# AUDIO.net
KiCad netlist of a schematic drawn in Altium Designer
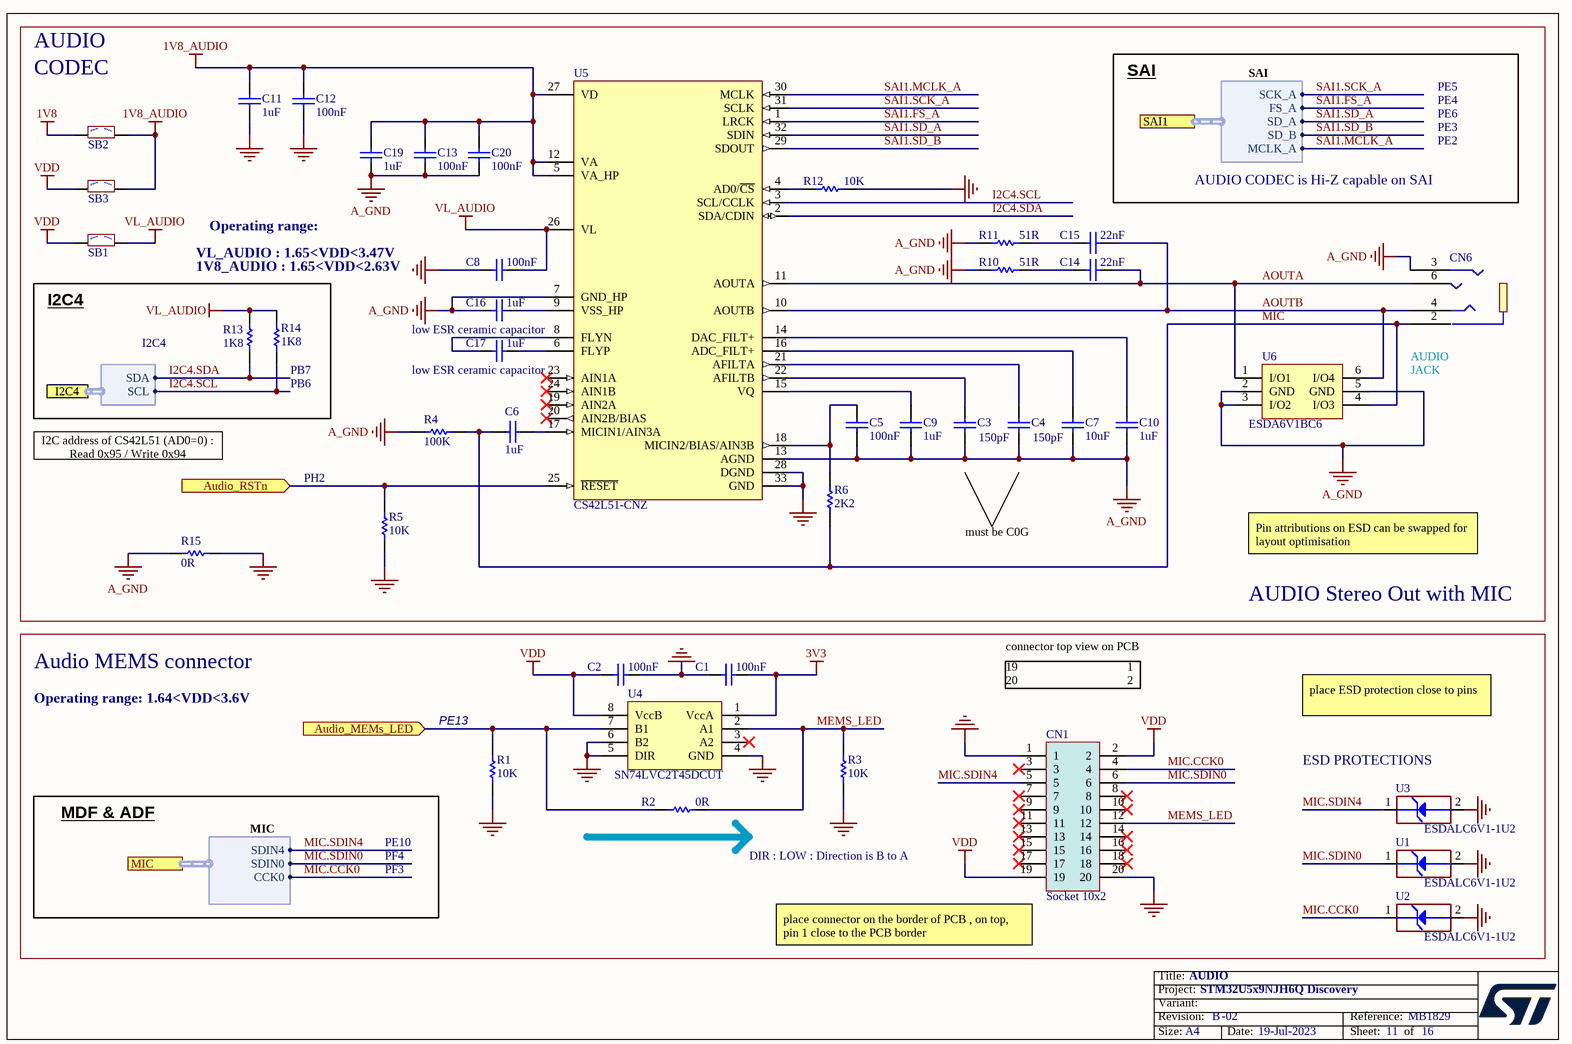
[diagram p0: AUDIO.SchDoc]

(export (version "E")
  (design (tool "Eeschema 10.0.6"))
  (components
    (comp (ref "C1")
      (value "100nF")
      (footprint "MCD_PARTS:C0402")
      (description "Capacitor, MLCC, 100nF, 16V, X7R, +/-10%, 0402, T=0.5mm")
      (fields
        (field (name "INTERNAL_PART_NUMBER") "MCD-00006")
        (field (name "MANUFACTURER_PART_NUMBER") "CC0402KRX7R7BB104")
      )
      (libsource (lib "MCD_PARTS_database") (part "Capacitor"))
    )
    (comp (ref "C2")
      (value "100nF")
      (footprint "MCD_PARTS:C0402")
      (description "Capacitor, MLCC, 100nF, 16V, X7R, +/-10%, 0402, T=0.5mm")
      (fields
        (field (name "INTERNAL_PART_NUMBER") "MCD-00006")
        (field (name "MANUFACTURER_PART_NUMBER") "CC0402KRX7R7BB104")
      )
      (libsource (lib "MCD_PARTS_database") (part "Capacitor"))
    )
    (comp (ref "C3")
      (value "150pF")
      (footprint "MCD_PARTS:C0603")
      (description "Capacitor, MLCC, 150pF, 50V, COG, +/-5%, 0603, T=0.8mm")
      (fields
        (field (name "INTERNAL_PART_NUMBER") "MCD-00304")
        (field (name "MANUFACTURER_PART_NUMBER") "CC0603JRNPO9BN151")
      )
      (libsource (lib "MCD_PARTS_database") (part "Capacitor"))
    )
    (comp (ref "C4")
      (value "150pF")
      (footprint "MCD_PARTS:C0603")
      (description "Capacitor, MLCC, 150pF, 50V, COG, +/-5%, 0603, T=0.8mm")
      (fields
        (field (name "INTERNAL_PART_NUMBER") "MCD-00304")
        (field (name "MANUFACTURER_PART_NUMBER") "CC0603JRNPO9BN151")
      )
      (libsource (lib "MCD_PARTS_database") (part "Capacitor"))
    )
    (comp (ref "C5")
      (value "100nF")
      (footprint "MCD_PARTS:C0402")
      (description "Capacitor, MLCC, 100nF, 16V, X7R, +/-10%, 0402, T=0.5mm")
      (fields
        (field (name "INTERNAL_PART_NUMBER") "MCD-00006")
        (field (name "MANUFACTURER_PART_NUMBER") "CC0402KRX7R7BB104")
      )
      (libsource (lib "MCD_PARTS_database") (part "Capacitor"))
    )
    (comp (ref "C6")
      (value "1uF")
      (footprint "MCD_PARTS:C0402")
      (description "Capacitor, MLCC, 1uF, 10V, X5R, +/-10%, 0402, T=0.5mm")
      (fields
        (field (name "INTERNAL_PART_NUMBER") "MCD-01722")
        (field (name "MANUFACTURER_PART_NUMBER") "CC0402KRX5R6BB105")
      )
      (libsource (lib "MCD_PARTS_database") (part "Capacitor"))
    )
    (comp (ref "C7")
      (value "10uF")
      (footprint "MCD_PARTS:C0603")
      (description "Capacitor, MLCC, 10uF, 6V3, X5R, +/-10%, 0603, T=0.8mm")
      (fields
        (field (name "INTERNAL_PART_NUMBER") "MCD-00243")
        (field (name "MANUFACTURER_PART_NUMBER") "CC0603KRX5R5BB106")
      )
      (libsource (lib "MCD_PARTS_database") (part "Capacitor"))
    )
    (comp (ref "C8")
      (value "100nF")
      (footprint "MCD_PARTS:C0402")
      (description "Capacitor, MLCC, 100nF, 16V, X7R, +/-10%, 0402, T=0.5mm")
      (fields
        (field (name "INTERNAL_PART_NUMBER") "MCD-00006")
        (field (name "MANUFACTURER_PART_NUMBER") "CC0402KRX7R7BB104")
      )
      (libsource (lib "MCD_PARTS_database") (part "Capacitor"))
    )
    (comp (ref "C9")
      (value "1uF")
      (footprint "MCD_PARTS:C0402")
      (description "Capacitor, MLCC, 1uF, 10V, X5R, +/-10%, 0402, T=0.5mm")
      (fields
        (field (name "INTERNAL_PART_NUMBER") "MCD-01722")
        (field (name "MANUFACTURER_PART_NUMBER") "CC0402KRX5R6BB105")
      )
      (libsource (lib "MCD_PARTS_database") (part "Capacitor"))
    )
    (comp (ref "C10")
      (value "1uF")
      (footprint "MCD_PARTS:C0402")
      (description "Capacitor, MLCC, 1uF, 10V, X5R, +/-10%, 0402, T=0.5mm")
      (fields
        (field (name "INTERNAL_PART_NUMBER") "MCD-01722")
        (field (name "MANUFACTURER_PART_NUMBER") "CC0402KRX5R6BB105")
      )
      (libsource (lib "MCD_PARTS_database") (part "Capacitor"))
    )
    (comp (ref "C11")
      (value "1uF")
      (footprint "MCD_PARTS:C0402")
      (description "Capacitor, MLCC, 1uF, 10V, X5R, +/-10%, 0402, T=0.5mm")
      (fields
        (field (name "INTERNAL_PART_NUMBER") "MCD-01722")
        (field (name "MANUFACTURER_PART_NUMBER") "CC0402KRX5R6BB105")
      )
      (libsource (lib "MCD_PARTS_database") (part "Capacitor"))
    )
    (comp (ref "C12")
      (value "100nF")
      (footprint "MCD_PARTS:C0402")
      (description "Capacitor, MLCC, 100nF, 16V, X7R, +/-10%, 0402, T=0.5mm")
      (fields
        (field (name "INTERNAL_PART_NUMBER") "MCD-00006")
        (field (name "MANUFACTURER_PART_NUMBER") "CC0402KRX7R7BB104")
      )
      (libsource (lib "MCD_PARTS_database") (part "Capacitor"))
    )
    (comp (ref "C13")
      (value "100nF")
      (footprint "MCD_PARTS:C0402")
      (description "Capacitor, MLCC, 100nF, 16V, X7R, +/-10%, 0402, T=0.5mm")
      (fields
        (field (name "INTERNAL_PART_NUMBER") "MCD-00006")
        (field (name "MANUFACTURER_PART_NUMBER") "CC0402KRX7R7BB104")
      )
      (libsource (lib "MCD_PARTS_database") (part "Capacitor"))
    )
    (comp (ref "C14")
      (value "22nF")
      (footprint "MCD_PARTS:C0402")
      (description "Capacitor, MLCC, 22nF, 16V, X7R, +/-10%, 0402, T=0.5mm")
      (fields
        (field (name "INTERNAL_PART_NUMBER") "MCD-00202")
        (field (name "MANUFACTURER_PART_NUMBER") "CC0402KRX7R7BB223")
      )
      (libsource (lib "MCD_PARTS_database") (part "Capacitor"))
    )
    (comp (ref "C15")
      (value "22nF")
      (footprint "MCD_PARTS:C0402")
      (description "Capacitor, MLCC, 22nF, 16V, X7R, +/-10%, 0402, T=0.5mm")
      (fields
        (field (name "INTERNAL_PART_NUMBER") "MCD-00202")
        (field (name "MANUFACTURER_PART_NUMBER") "CC0402KRX7R7BB223")
      )
      (libsource (lib "MCD_PARTS_database") (part "Capacitor"))
    )
    (comp (ref "C16")
      (value "1uF")
      (footprint "MCD_PARTS:C0603")
      (description "Capacitor, MLCC, 1uF, 16V, X5R, +/-10%, 0603, T=0.8mm")
      (fields
        (field (name "INTERNAL_PART_NUMBER") "MCD-00010")
        (field (name "MANUFACTURER_PART_NUMBER") "CC0603KRX5R7BB105")
      )
      (libsource (lib "MCD_PARTS_database") (part "Capacitor"))
    )
    (comp (ref "C17")
      (value "1uF")
      (footprint "MCD_PARTS:C0603")
      (description "Capacitor, MLCC, 1uF, 16V, X5R, +/-10%, 0603, T=0.8mm")
      (fields
        (field (name "INTERNAL_PART_NUMBER") "MCD-00010")
        (field (name "MANUFACTURER_PART_NUMBER") "CC0603KRX5R7BB105")
      )
      (libsource (lib "MCD_PARTS_database") (part "Capacitor"))
    )
    (comp (ref "C19")
      (value "1uF")
      (footprint "MCD_PARTS:C0402")
      (description "Capacitor, MLCC, 1uF, 10V, X5R, +/-10%, 0402, T=0.5mm")
      (fields
        (field (name "INTERNAL_PART_NUMBER") "MCD-01722")
        (field (name "MANUFACTURER_PART_NUMBER") "CC0402KRX5R6BB105")
      )
      (libsource (lib "MCD_PARTS_database") (part "Capacitor"))
    )
    (comp (ref "C20")
      (value "100nF")
      (footprint "MCD_PARTS:C0402")
      (description "Capacitor, MLCC, 100nF, 16V, X7R, +/-10%, 0402, T=0.5mm")
      (fields
        (field (name "INTERNAL_PART_NUMBER") "MCD-00006")
        (field (name "MANUFACTURER_PART_NUMBER") "CC0402KRX7R7BB104")
      )
      (libsource (lib "MCD_PARTS_database") (part "Capacitor"))
    )
    (comp (ref "CN1")
      (value "Socket 10x2")
      (footprint "MCD_PARTS:CON_FCI_20021311-XXX20XXLF")
      (description "Socket, 10x2, 1.27mm, VR, TH, T=4.30mm/2.40mm")
      (fields (field (name "INTERNAL_PART_NUMBER") "MCD-00147") (field (name "MANUFACTURER") "AMPHENOL ICC"))
      (libsource (lib "MCD_PARTS_database") (part "Socket 10x2"))
    )
    (comp (ref "CN6")
      (value "Jack_PJ3028B-3_4P")
      (footprint "MCD_PARTS:CON_PHONE-JACK-3P5_HY_PJ3028B")
      (description "Jack_ Socket-Stereo, 3.5mm, 4 pins, RA, SMD, T=5mm")
      (fields
        (field (name "INTERNAL_PART_NUMBER") "MCD-00263")
        (field (name "MANUFACTURER_PART_NUMBER") "PJ3028B-3_4P")
      )
      (libsource (lib "MCD_PARTS_database") (part "Jack_PJ3028B-3_4P"))
    )
    (comp (ref "R1")
      (value "10K")
      (footprint "MCD_PARTS:R0402")
      (description "Resistor, 10K, 0402, +/-1%, 1/16W")
      (fields
        (field (name "INTERNAL_PART_NUMBER") "MCD-00053")
        (field (name "MANUFACTURER_PART_NUMBER") "RC0402FR-0710KL")
      )
      (libsource (lib "MCD_PARTS_database") (part "Resistor"))
    )
    (comp (ref "R2")
      (value "0R")
      (footprint "MCD_PARTS:R0402")
      (description "Resistor, 0R, 0402, +/-5%, 1/16W")
      (fields
        (field (name "INTERNAL_PART_NUMBER") "MCD-00052")
        (field (name "MANUFACTURER_PART_NUMBER") "RC0402JR-070RL")
      )
      (libsource (lib "MCD_PARTS_database") (part "Resistor"))
    )
    (comp (ref "R3")
      (value "10K")
      (footprint "MCD_PARTS:R0402")
      (description "Resistor, 10K, 0402, +/-1%, 1/16W")
      (fields
        (field (name "INTERNAL_PART_NUMBER") "MCD-00053")
        (field (name "MANUFACTURER_PART_NUMBER") "RC0402FR-0710KL")
      )
      (libsource (lib "MCD_PARTS_database") (part "Resistor"))
    )
    (comp (ref "R4")
      (value "100K")
      (footprint "MCD_PARTS:R0402")
      (description "Resistor, 100K, 0402, +/-1%, 1/16W")
      (fields
        (field (name "INTERNAL_PART_NUMBER") "MCD-00059")
        (field (name "MANUFACTURER_PART_NUMBER") "RC0402FR-07100KL")
      )
      (libsource (lib "MCD_PARTS_database") (part "Resistor"))
    )
    (comp (ref "R5")
      (value "10K")
      (footprint "MCD_PARTS:R0402")
      (description "Resistor, 10K, 0402, +/-1%, 1/16W")
      (fields
        (field (name "INTERNAL_PART_NUMBER") "MCD-00053")
        (field (name "MANUFACTURER_PART_NUMBER") "RC0402FR-0710KL")
      )
      (libsource (lib "MCD_PARTS_database") (part "Resistor"))
    )
    (comp (ref "R6")
      (value "2K2")
      (footprint "MCD_PARTS:R0402")
      (description "Resistor, 2K2, 0402, +/-1%, 1/16W")
      (fields
        (field (name "INTERNAL_PART_NUMBER") "MCD-00057")
        (field (name "MANUFACTURER_PART_NUMBER") "RC0402FR-072K2L")
      )
      (libsource (lib "MCD_PARTS_database") (part "Resistor"))
    )
    (comp (ref "R10")
      (value "51R")
      (footprint "MCD_PARTS:R0402")
      (description "Resistor, 51R, 0402, +/-1%, 1/16W")
      (fields
        (field (name "INTERNAL_PART_NUMBER") "MCD-00485")
        (field (name "MANUFACTURER_PART_NUMBER") "RC0402FR-0751RL")
      )
      (libsource (lib "MCD_PARTS_database") (part "Resistor"))
    )
    (comp (ref "R11")
      (value "51R")
      (footprint "MCD_PARTS:R0402")
      (description "Resistor, 51R, 0402, +/-1%, 1/16W")
      (fields
        (field (name "INTERNAL_PART_NUMBER") "MCD-00485")
        (field (name "MANUFACTURER_PART_NUMBER") "RC0402FR-0751RL")
      )
      (libsource (lib "MCD_PARTS_database") (part "Resistor"))
    )
    (comp (ref "R12")
      (value "10K")
      (footprint "MCD_PARTS:R0402")
      (description "Resistor, 10K, 0402, +/-1%, 1/16W")
      (fields
        (field (name "INTERNAL_PART_NUMBER") "MCD-00053")
        (field (name "MANUFACTURER_PART_NUMBER") "RC0402FR-0710KL")
      )
      (libsource (lib "MCD_PARTS_database") (part "Resistor"))
    )
    (comp (ref "R13")
      (value "1K8")
      (footprint "MCD_PARTS:R0402")
      (description "Resistor, 1K8, 0402, +/-1%, 1/16W")
      (fields
        (field (name "INTERNAL_PART_NUMBER") "MCD-00409")
        (field (name "MANUFACTURER_PART_NUMBER") "RC0402FR-071K8L")
      )
      (libsource (lib "MCD_PARTS_database") (part "Resistor"))
    )
    (comp (ref "R14")
      (value "1K8")
      (footprint "MCD_PARTS:R0402")
      (description "Resistor, 1K8, 0402, +/-1%, 1/16W")
      (fields
        (field (name "INTERNAL_PART_NUMBER") "MCD-00409")
        (field (name "MANUFACTURER_PART_NUMBER") "RC0402FR-071K8L")
      )
      (libsource (lib "MCD_PARTS_database") (part "Resistor"))
    )
    (comp (ref "R15")
      (value "0R")
      (footprint "MCD_PARTS:R0402")
      (description "Resistor, 0R, 0402, +/-5%, 1/16W")
      (fields
        (field (name "INTERNAL_PART_NUMBER") "MCD-00052")
        (field (name "MANUFACTURER_PART_NUMBER") "RC0402JR-070RL")
      )
      (libsource (lib "MCD_PARTS_database") (part "Resistor"))
    )
    (comp (ref "SB1")
      (value "SB_OFF")
      (footprint "MCD_PARTS:SOLDER-BRIDGE_R0402-0R")
      (description "Solder Bridge 0402 OFF")
      (fields
        (field (name "INTERNAL_PART_NUMBER") "MCD-02162")
        (field (name "MANUFACTURER_PART_NUMBER") "RC0402JR-070RL")
      )
      (libsource (lib "MCD_PARTS_database") (part "SB_OFF"))
    )
    (comp (ref "SB2")
      (value "SB_OFF")
      (footprint "MCD_PARTS:SOLDER-BRIDGE_R0402-0R")
      (description "Solder Bridge 0402 OFF")
      (fields
        (field (name "INTERNAL_PART_NUMBER") "MCD-02162")
        (field (name "MANUFACTURER_PART_NUMBER") "RC0402JR-070RL")
      )
      (libsource (lib "MCD_PARTS_database") (part "SB_OFF"))
    )
    (comp (ref "SB3")
      (value "SB_OFF")
      (footprint "MCD_PARTS:SOLDER-BRIDGE_R0402-0R")
      (description "Solder Bridge 0402 OFF")
      (fields
        (field (name "INTERNAL_PART_NUMBER") "MCD-02162")
        (field (name "MANUFACTURER_PART_NUMBER") "RC0402JR-070RL")
      )
      (libsource (lib "MCD_PARTS_database") (part "SB_OFF"))
    )
    (comp (ref "U1")
      (value "ESDALC6V1-1U2")
      (footprint "MCD_PARTS:ESD_ST0201")
      (description "ESD protection 6V1")
      (fields
        (field (name "INTERNAL_PART_NUMBER") "MCD-00170")
        (field (name "MANUFACTURER") "STMICROELECTRONICS")
      )
      (libsource (lib "MCD_PARTS_database") (part "ESD-TRANSIL"))
    )
    (comp (ref "U2")
      (value "ESDALC6V1-1U2")
      (footprint "MCD_PARTS:ESD_ST0201")
      (description "ESD protection 6V1")
      (fields
        (field (name "INTERNAL_PART_NUMBER") "MCD-00170")
        (field (name "MANUFACTURER") "STMICROELECTRONICS")
      )
      (libsource (lib "MCD_PARTS_database") (part "ESD-TRANSIL"))
    )
    (comp (ref "U3")
      (value "ESDALC6V1-1U2")
      (footprint "MCD_PARTS:ESD_ST0201")
      (description "ESD protection 6V1")
      (fields
        (field (name "INTERNAL_PART_NUMBER") "MCD-00170")
        (field (name "MANUFACTURER") "STMICROELECTRONICS")
      )
      (libsource (lib "MCD_PARTS_database") (part "ESD-TRANSIL"))
    )
    (comp (ref "U4")
      (value "SN74LVC2T45DCUT")
      (footprint "MCD_PARTS:ICC_VSSOP8_DCU_R-PDSO-G8_2X2P30_P050")
      (description "Dual bit dual supply bus transceiver")
      (fields
        (field (name "INTERNAL_PART_NUMBER") "MCD-00264")
        (field (name "MANUFACTURER") "TEXAS INSTRUMENTS")
      )
      (libsource (lib "MCD_PARTS_database") (part "SN74LVC2T45DCUT"))
    )
    (comp (ref "U5")
      (value "CS42L51-CNZ")
      (footprint "MCD_PARTS:ICC_QFN32-EPAD_5X5_P050")
      (description "Low-Power, Stereo Codec with Headphone Amp")
      (fields (field (name "INTERNAL_PART_NUMBER") "MCD-00265") (field (name "MANUFACTURER") "CIRRUS LOGIC"))
      (libsource (lib "MCD_PARTS_database") (part "CS42L51-CNZ"))
    )
    (comp (ref "U6")
      (value "ESDA6V1BC6")
      (footprint "MCD_PARTS:ESD_SOT23-6L")
      (description "Quad Bidir ESD protection")
      (fields
        (field (name "INTERNAL_PART_NUMBER") "MCD-00247")
        (field (name "MANUFACTURER") "STMICROELECTRONICS")
      )
      (libsource (lib "MCD_PARTS_database") (part "ESDA6V1BC6"))
    )
  )
  (nets
    (net (code "3") (name "/AOUTA") (class "Default")
      (node (ref "C14") (pin "2") (pinfunction "2_2") (pintype "passive"))
      (node (ref "CN6") (pin "6") (pintype "passive"))
      (node (ref "U5") (pin "11") (pinfunction "AOUTA_11") (pintype "output"))
      (node (ref "U6") (pin "1") (pinfunction "I/O1_1") (pintype "passive"))
    )
    (net (code "4") (name "/AOUTB") (class "Default")
      (node (ref "C15") (pin "2") (pinfunction "2_2") (pintype "passive"))
      (node (ref "CN6") (pin "4") (pintype "passive"))
      (node (ref "U5") (pin "10") (pinfunction "AOUTB_10") (pintype "output"))
      (node (ref "U6") (pin "6") (pinfunction "I/O4_6") (pintype "passive"))
    )
    (net (code "5") (name "/Audio_MEMs_LED") (class "Default")
      (node (ref "R1") (pin "2") (pinfunction "2_2") (pintype "passive"))
      (node (ref "R2") (pin "1") (pinfunction "1_1") (pintype "passive"))
      (node (ref "U4") (pin "7") (pinfunction "B1_7") (pintype "passive"))
    )
    (net (code "6") (name "/Audio_RSTn") (class "Default")
      (node (ref "R5") (pin "2") (pinfunction "2_2") (pintype "passive"))
      (node (ref "U5") (pin "25") (pinfunction "~{RESET}_25") (pintype "input"))
    )
    (net (code "7") (name "/I2C4.SCL") (class "Default")
      (node (ref "R14") (pin "1") (pinfunction "1_1") (pintype "passive"))
      (node (ref "U5") (pin "3") (pinfunction "SCL/CCLK_3") (pintype "input"))
    )
    (net (code "8") (name "/I2C4.SDA") (class "Default")
      (node (ref "R13") (pin "1") (pinfunction "1_1") (pintype "passive"))
      (node (ref "U5") (pin "2") (pinfunction "SDA/CDIN_2") (pintype "bidirectional"))
    )
    (net (code "9") (name "/MEMS_LED") (class "Default")
      (node (ref "CN1") (pin "12") (pinfunction "12_12") (pintype "passive"))
      (node (ref "R2") (pin "2") (pinfunction "2_2") (pintype "passive"))
      (node (ref "R3") (pin "2") (pinfunction "2_2") (pintype "passive"))
      (node (ref "U4") (pin "2") (pinfunction "A1_2") (pintype "passive"))
    )
    (net (code "10") (name "/MIC") (class "Default")
      (node (ref "C6") (pin "1") (pinfunction "1_1") (pintype "passive"))
      (node (ref "CN6") (pin "2") (pintype "passive"))
      (node (ref "R4") (pin "2") (pinfunction "2_2") (pintype "passive"))
      (node (ref "R6") (pin "1") (pinfunction "1_1") (pintype "passive"))
      (node (ref "U6") (pin "4") (pinfunction "I/O3_4") (pintype "passive"))
    )
    (net (code "11") (name "/MIC.CCK0") (class "Default")
      (node (ref "CN1") (pin "4") (pinfunction "4_4") (pintype "passive"))
      (node (ref "U2") (pin "1") (pinfunction "IO1_1") (pintype "passive"))
    )
    (net (code "12") (name "/MIC.SDIN0") (class "Default")
      (node (ref "CN1") (pin "6") (pinfunction "6_6") (pintype "passive"))
      (node (ref "U1") (pin "1") (pinfunction "IO1_1") (pintype "passive"))
    )
    (net (code "13") (name "/MIC.SDIN4") (class "Default")
      (node (ref "CN1") (pin "5") (pinfunction "5_5") (pintype "passive"))
      (node (ref "U3") (pin "1") (pinfunction "IO1_1") (pintype "passive"))
    )
    (net (code "14") (name "/SAI1.FS_A") (class "Default")
      (node (ref "U5") (pin "1") (pinfunction "LRCK_1") (pintype "input"))
    )
    (net (code "15") (name "/SAI1.MCLK_A") (class "Default")
      (node (ref "U5") (pin "30") (pinfunction "MCLK_30") (pintype "input"))
    )
    (net (code "16") (name "/SAI1.SCK_A") (class "Default")
      (node (ref "U5") (pin "31") (pinfunction "SCLK_31") (pintype "input"))
    )
    (net (code "17") (name "/SAI1.SD_A") (class "Default")
      (node (ref "U5") (pin "32") (pinfunction "SDIN_32") (pintype "input"))
    )
    (net (code "18") (name "/SAI1.SD_B") (class "Default")
      (node (ref "U5") (pin "29") (pinfunction "SDOUT_29") (pintype "output"))
    )
    (net (code "22") (name "1V8") (class "Default")
      (node (ref "SB2") (pin "1") (pinfunction "1_1") (pintype "passive"))
    )
    (net (code "23") (name "1V8_AUDIO") (class "Default")
      (node (ref "C11") (pin "2") (pinfunction "2_2") (pintype "passive"))
      (node (ref "C12") (pin "2") (pinfunction "2_2") (pintype "passive"))
      (node (ref "C13") (pin "2") (pinfunction "2_2") (pintype "passive"))
      (node (ref "C19") (pin "2") (pinfunction "2_2") (pintype "passive"))
      (node (ref "C20") (pin "2") (pinfunction "2_2") (pintype "passive"))
      (node (ref "SB2") (pin "2") (pinfunction "2_2") (pintype "passive"))
      (node (ref "SB3") (pin "2") (pinfunction "2_2") (pintype "passive"))
      (node (ref "U5") (pin "12") (pinfunction "VA_12") (pintype "power_in"))
      (node (ref "U5") (pin "27") (pinfunction "VD_27") (pintype "power_in"))
      (node (ref "U5") (pin "5") (pinfunction "VA_HP_5") (pintype "power_in"))
    )
    (net (code "24") (name "3V3") (class "Default")
      (node (ref "C1") (pin "2") (pinfunction "2_2") (pintype "passive"))
      (node (ref "U4") (pin "1") (pinfunction "VccA_1") (pintype "power_in"))
    )
    (net (code "25") (name "A_GND") (class "Default")
      (node (ref "C10") (pin "1") (pinfunction "1_1") (pintype "passive"))
      (node (ref "C13") (pin "1") (pinfunction "1_1") (pintype "passive"))
      (node (ref "C16") (pin "1") (pinfunction "1_1") (pintype "passive"))
      (node (ref "C19") (pin "1") (pinfunction "1_1") (pintype "passive"))
      (node (ref "C20") (pin "1") (pinfunction "1_1") (pintype "passive"))
      (node (ref "C3") (pin "1") (pinfunction "1_1") (pintype "passive"))
      (node (ref "C4") (pin "1") (pinfunction "1_1") (pintype "passive"))
      (node (ref "C5") (pin "1") (pinfunction "1_1") (pintype "passive"))
      (node (ref "C7") (pin "1") (pinfunction "1_1") (pintype "passive"))
      (node (ref "C9") (pin "1") (pinfunction "1_1") (pintype "passive"))
      (node (ref "CN6") (pin "3") (pintype "passive"))
      (node (ref "R10") (pin "1") (pinfunction "1_1") (pintype "passive"))
      (node (ref "R11") (pin "1") (pinfunction "1_1") (pintype "passive"))
      (node (ref "R15") (pin "1") (pinfunction "1_1") (pintype "passive"))
      (node (ref "R4") (pin "1") (pinfunction "1_1") (pintype "passive"))
      (node (ref "U5") (pin "13") (pinfunction "AGND_13") (pintype "power_in"))
      (node (ref "U5") (pin "7") (pinfunction "GND_HP_7") (pintype "power_in"))
      (node (ref "U6") (pin "2") (pinfunction "GND_2") (pintype "passive"))
      (node (ref "U6") (pin "3") (pinfunction "I/O2_3") (pintype "passive"))
      (node (ref "U6") (pin "5") (pinfunction "GND_5") (pintype "passive"))
    )
    (net (code "26") (name "GND") (class "Default")
      (node (ref "C1") (pin "1") (pinfunction "1_1") (pintype "passive"))
      (node (ref "C11") (pin "1") (pinfunction "1_1") (pintype "passive"))
      (node (ref "C12") (pin "1") (pinfunction "1_1") (pintype "passive"))
      (node (ref "C2") (pin "2") (pinfunction "2_2") (pintype "passive"))
      (node (ref "C8") (pin "2") (pinfunction "2_2") (pintype "passive"))
      (node (ref "CN1") (pin "1") (pinfunction "1_1") (pintype "passive"))
      (node (ref "CN1") (pin "20") (pinfunction "20_20") (pintype "passive"))
      (node (ref "R1") (pin "1") (pinfunction "1_1") (pintype "passive"))
      (node (ref "R12") (pin "2") (pinfunction "2_2") (pintype "passive"))
      (node (ref "R15") (pin "2") (pinfunction "2_2") (pintype "passive"))
      (node (ref "R3") (pin "1") (pinfunction "1_1") (pintype "passive"))
      (node (ref "R5") (pin "1") (pinfunction "1_1") (pintype "passive"))
      (node (ref "U1") (pin "2") (pinfunction "GND_2") (pintype "passive"))
      (node (ref "U2") (pin "2") (pinfunction "GND_2") (pintype "passive"))
      (node (ref "U3") (pin "2") (pinfunction "GND_2") (pintype "passive"))
      (node (ref "U4") (pin "4") (pinfunction "GND_4") (pintype "power_in"))
      (node (ref "U4") (pin "5") (pinfunction "DIR_5") (pintype "passive"))
      (node (ref "U4") (pin "6") (pinfunction "B2_6") (pintype "passive"))
      (node (ref "U5") (pin "28") (pinfunction "DGND_28") (pintype "power_in"))
      (node (ref "U5") (pin "33") (pinfunction "GND_33") (pintype "power_in"))
    )
    (net (code "27") (name "Net-(C14-Pad1)") (class "Default")
      (node (ref "C14") (pin "1") (pinfunction "1_1") (pintype "passive"))
      (node (ref "R10") (pin "2") (pinfunction "2_2") (pintype "passive"))
    )
    (net (code "28") (name "Net-(C15-Pad1)") (class "Default")
      (node (ref "C15") (pin "1") (pinfunction "1_1") (pintype "passive"))
      (node (ref "R11") (pin "2") (pinfunction "2_2") (pintype "passive"))
    )
    (net (code "29") (name "Net-(U5-AD0{slash}~{CS})") (class "Default")
      (node (ref "R12") (pin "1") (pinfunction "1_1") (pintype "passive"))
      (node (ref "U5") (pin "4") (pinfunction "AD0/~{CS}_4") (pintype "input"))
    )
    (net (code "30") (name "Net-(U5-ADC_FILT+)") (class "Default")
      (node (ref "C7") (pin "2") (pinfunction "2_2") (pintype "passive"))
      (node (ref "U5") (pin "16") (pinfunction "ADC_FILT+_16") (pintype "power_in"))
    )
    (net (code "31") (name "Net-(U5-AFILTA)") (class "Default")
      (node (ref "C4") (pin "2") (pinfunction "2_2") (pintype "passive"))
      (node (ref "U5") (pin "21") (pinfunction "AFILTA_21") (pintype "output"))
    )
    (net (code "32") (name "Net-(U5-AFILTB)") (class "Default")
      (node (ref "C3") (pin "2") (pinfunction "2_2") (pintype "passive"))
      (node (ref "U5") (pin "22") (pinfunction "AFILTB_22") (pintype "output"))
    )
    (net (code "33") (name "Net-(U5-DAC_FILT+)") (class "Default")
      (node (ref "C10") (pin "2") (pinfunction "2_2") (pintype "passive"))
      (node (ref "U5") (pin "14") (pinfunction "DAC_FILT+_14") (pintype "power_in"))
    )
    (net (code "34") (name "Net-(U5-FLYN)") (class "Default")
      (node (ref "C17") (pin "1") (pinfunction "1_1") (pintype "passive"))
      (node (ref "U5") (pin "8") (pinfunction "FLYN_8") (pintype "passive"))
    )
    (net (code "35") (name "Net-(U5-FLYP)") (class "Default")
      (node (ref "C17") (pin "2") (pinfunction "2_2") (pintype "passive"))
      (node (ref "U5") (pin "6") (pinfunction "FLYP_6") (pintype "passive"))
    )
    (net (code "36") (name "Net-(U5-MICIN1{slash}AIN3A)") (class "Default")
      (node (ref "C6") (pin "2") (pinfunction "2_2") (pintype "passive"))
      (node (ref "U5") (pin "17") (pinfunction "MICIN1/AIN3A_17") (pintype "input"))
    )
    (net (code "37") (name "Net-(U5-MICIN2{slash}BIAS{slash}AIN3B)") (class "Default")
      (node (ref "C5") (pin "2") (pinfunction "2_2") (pintype "passive"))
      (node (ref "R6") (pin "2") (pinfunction "2_2") (pintype "passive"))
      (node (ref "U5") (pin "18") (pinfunction "MICIN2/BIAS/AIN3B_18") (pintype "output"))
    )
    (net (code "38") (name "Net-(U5-VQ)") (class "Default")
      (node (ref "C9") (pin "2") (pinfunction "2_2") (pintype "passive"))
      (node (ref "U5") (pin "15") (pinfunction "VQ_15") (pintype "power_in"))
    )
    (net (code "39") (name "Net-(U5-VSS_HP)") (class "Default")
      (node (ref "C16") (pin "2") (pinfunction "2_2") (pintype "passive"))
      (node (ref "U5") (pin "9") (pinfunction "VSS_HP_9") (pintype "power_in"))
    )
    (net (code "40") (name "VDD") (class "Default")
      (node (ref "C2") (pin "1") (pinfunction "1_1") (pintype "passive"))
      (node (ref "CN1") (pin "19") (pinfunction "19_19") (pintype "passive"))
      (node (ref "CN1") (pin "2") (pinfunction "2_2") (pintype "passive"))
      (node (ref "SB1") (pin "1") (pinfunction "1_1") (pintype "passive"))
      (node (ref "SB3") (pin "1") (pinfunction "1_1") (pintype "passive"))
      (node (ref "U4") (pin "8") (pinfunction "VccB_8") (pintype "power_in"))
    )
    (net (code "41") (name "VL_AUDIO") (class "Default")
      (node (ref "C8") (pin "1") (pinfunction "1_1") (pintype "passive"))
      (node (ref "R13") (pin "2") (pinfunction "2_2") (pintype "passive"))
      (node (ref "R14") (pin "2") (pinfunction "2_2") (pintype "passive"))
      (node (ref "SB1") (pin "2") (pinfunction "2_2") (pintype "passive"))
      (node (ref "U5") (pin "26") (pinfunction "VL_26") (pintype "power_in"))
    )
    (net (code "42") (name "unconnected-(CN1-Pad3)") (class "Default")
      (node (ref "CN1") (pin "3") (pinfunction "3_3") (pintype "passive+no_connect"))
    )
    (net (code "43") (name "unconnected-(CN1-Pad7)") (class "Default")
      (node (ref "CN1") (pin "7") (pinfunction "7_7") (pintype "passive+no_connect"))
    )
    (net (code "44") (name "unconnected-(CN1-Pad8)") (class "Default")
      (node (ref "CN1") (pin "8") (pinfunction "8_8") (pintype "passive+no_connect"))
    )
    (net (code "45") (name "unconnected-(CN1-Pad9)") (class "Default")
      (node (ref "CN1") (pin "9") (pinfunction "9_9") (pintype "passive+no_connect"))
    )
    (net (code "46") (name "unconnected-(CN1-Pad10)") (class "Default")
      (node (ref "CN1") (pin "10") (pinfunction "10_10") (pintype "passive+no_connect"))
    )
    (net (code "47") (name "unconnected-(CN1-Pad11)") (class "Default")
      (node (ref "CN1") (pin "11") (pinfunction "11_11") (pintype "passive+no_connect"))
    )
    (net (code "48") (name "unconnected-(CN1-Pad13)") (class "Default")
      (node (ref "CN1") (pin "13") (pinfunction "13_13") (pintype "passive+no_connect"))
    )
    (net (code "49") (name "unconnected-(CN1-Pad14)") (class "Default")
      (node (ref "CN1") (pin "14") (pinfunction "14_14") (pintype "passive+no_connect"))
    )
    (net (code "50") (name "unconnected-(CN1-Pad15)") (class "Default")
      (node (ref "CN1") (pin "15") (pinfunction "15_15") (pintype "passive+no_connect"))
    )
    (net (code "51") (name "unconnected-(CN1-Pad16)") (class "Default")
      (node (ref "CN1") (pin "16") (pinfunction "16_16") (pintype "passive+no_connect"))
    )
    (net (code "52") (name "unconnected-(CN1-Pad17)") (class "Default")
      (node (ref "CN1") (pin "17") (pinfunction "17_17") (pintype "passive+no_connect"))
    )
    (net (code "53") (name "unconnected-(CN1-Pad18)") (class "Default")
      (node (ref "CN1") (pin "18") (pinfunction "18_18") (pintype "passive+no_connect"))
    )
    (net (code "54") (name "unconnected-(U4-A2-Pad3)") (class "Default")
      (node (ref "U4") (pin "3") (pinfunction "A2_3") (pintype "passive+no_connect"))
    )
    (net (code "55") (name "unconnected-(U5-AIN1A-Pad23)") (class "Default")
      (node (ref "U5") (pin "23") (pinfunction "AIN1A_23") (pintype "input+no_connect"))
    )
    (net (code "56") (name "unconnected-(U5-AIN1B-Pad24)") (class "Default")
      (node (ref "U5") (pin "24") (pinfunction "AIN1B_24") (pintype "input+no_connect"))
    )
    (net (code "57") (name "unconnected-(U5-AIN2A-Pad19)") (class "Default")
      (node (ref "U5") (pin "19") (pinfunction "AIN2A_19") (pintype "input+no_connect"))
    )
    (net (code "58") (name "unconnected-(U5-AIN2B{slash}BIAS-Pad20)") (class "Default")
      (node (ref "U5") (pin "20") (pinfunction "AIN2B/BIAS_20") (pintype "output+no_connect"))
    )
  )
)
